# digitalBlock.net
KiCad netlist of a schematic drawn in Altium Designer
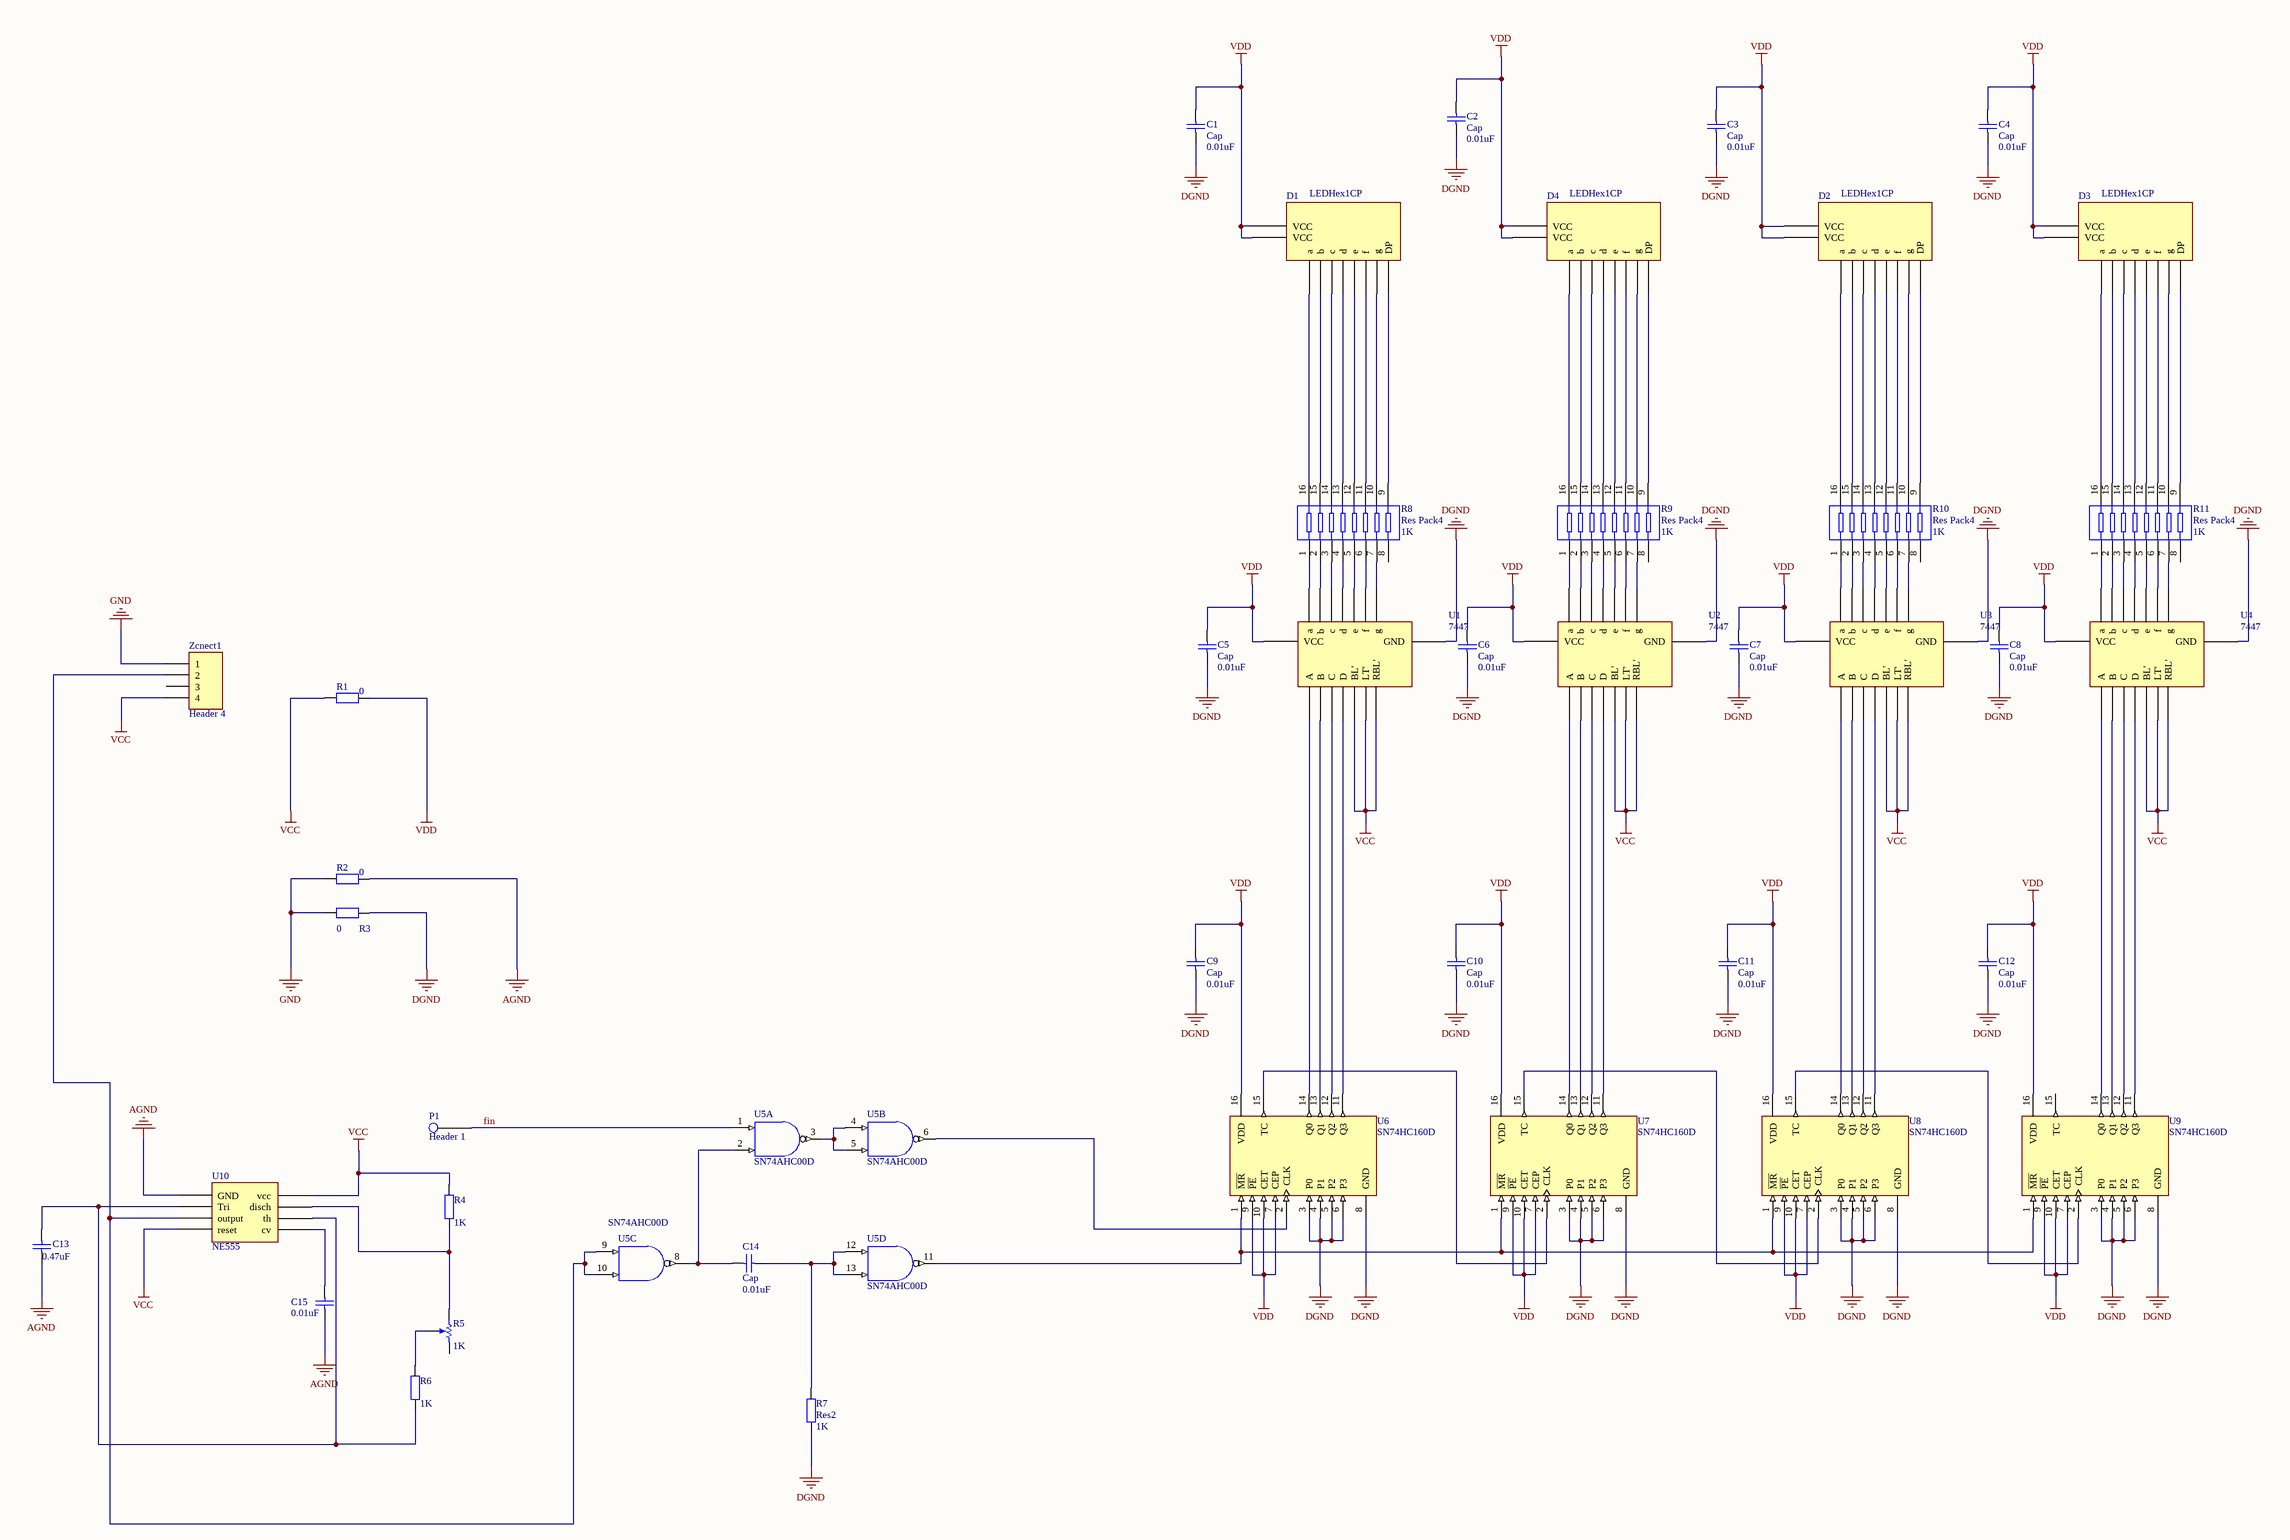
[diagram p0: digitalBlock.SchDoc]

(export (version "E")
  (design (tool "Eeschema 10.0.6"))
  (components
    (comp (ref "C1")
      (value "Cap")
      (footprint "CAP-0603")
      (description "Capacitor")
      (fields (field (name "ALTIUM_VALUE") "0.01uF") (field (name "PUBLISHER") "Altium Limited"))
      (libsource (lib "Miscellaneous Devices") (part "Cap"))
    )
    (comp (ref "C2")
      (value "Cap")
      (footprint "CAP-0603")
      (description "Capacitor")
      (fields (field (name "ALTIUM_VALUE") "0.01uF") (field (name "PUBLISHER") "Altium Limited"))
      (libsource (lib "Miscellaneous Devices") (part "Cap"))
    )
    (comp (ref "C3")
      (value "Cap")
      (footprint "CAP-0603")
      (description "Capacitor")
      (fields (field (name "ALTIUM_VALUE") "0.01uF") (field (name "PUBLISHER") "Altium Limited"))
      (libsource (lib "Miscellaneous Devices") (part "Cap"))
    )
    (comp (ref "C4")
      (value "Cap")
      (footprint "CAP-0603")
      (description "Capacitor")
      (fields (field (name "ALTIUM_VALUE") "0.01uF") (field (name "PUBLISHER") "Altium Limited"))
      (libsource (lib "Miscellaneous Devices") (part "Cap"))
    )
    (comp (ref "C5")
      (value "Cap")
      (footprint "CAP-0603")
      (description "Capacitor")
      (fields (field (name "ALTIUM_VALUE") "0.01uF") (field (name "PUBLISHER") "Altium Limited"))
      (libsource (lib "Miscellaneous Devices") (part "Cap"))
    )
    (comp (ref "C6")
      (value "Cap")
      (footprint "CAP-0603")
      (description "Capacitor")
      (fields (field (name "ALTIUM_VALUE") "0.01uF") (field (name "PUBLISHER") "Altium Limited"))
      (libsource (lib "Miscellaneous Devices") (part "Cap"))
    )
    (comp (ref "C7")
      (value "Cap")
      (footprint "CAP-0603")
      (description "Capacitor")
      (fields (field (name "ALTIUM_VALUE") "0.01uF") (field (name "PUBLISHER") "Altium Limited"))
      (libsource (lib "Miscellaneous Devices") (part "Cap"))
    )
    (comp (ref "C8")
      (value "Cap")
      (footprint "CAP-0603")
      (description "Capacitor")
      (fields (field (name "ALTIUM_VALUE") "0.01uF") (field (name "PUBLISHER") "Altium Limited"))
      (libsource (lib "Miscellaneous Devices") (part "Cap"))
    )
    (comp (ref "C9")
      (value "Cap")
      (footprint "CAP-0603")
      (description "Capacitor")
      (fields (field (name "ALTIUM_VALUE") "0.01uF") (field (name "PUBLISHER") "Altium Limited"))
      (libsource (lib "Miscellaneous Devices") (part "Cap"))
    )
    (comp (ref "C10")
      (value "Cap")
      (footprint "CAP-0603")
      (description "Capacitor")
      (fields (field (name "ALTIUM_VALUE") "0.01uF") (field (name "PUBLISHER") "Altium Limited"))
      (libsource (lib "Miscellaneous Devices") (part "Cap"))
    )
    (comp (ref "C11")
      (value "Cap")
      (footprint "CAP-0603")
      (description "Capacitor")
      (fields (field (name "ALTIUM_VALUE") "0.01uF") (field (name "PUBLISHER") "Altium Limited"))
      (libsource (lib "Miscellaneous Devices") (part "Cap"))
    )
    (comp (ref "C12")
      (value "Cap")
      (footprint "CAP-0603")
      (description "Capacitor")
      (fields (field (name "ALTIUM_VALUE") "0.01uF") (field (name "PUBLISHER") "Altium Limited"))
      (libsource (lib "Miscellaneous Devices") (part "Cap"))
    )
    (comp (ref "C13")
      (value "0.47uF")
      (footprint "CAP-0603")
      (description "Capacitor")
      (fields (field (name "Comment") "Cap") (field (name "PUBLISHER") "Altium Limited"))
      (libsource (lib "Miscellaneous Devices") (part "Cap"))
    )
    (comp (ref "C14")
      (value "Cap")
      (footprint "CAP-0603")
      (description "Capacitor")
      (fields (field (name "ALTIUM_VALUE") "0.01uF") (field (name "PUBLISHER") "Altium Limited"))
      (libsource (lib "Miscellaneous Devices") (part "Cap"))
    )
    (comp (ref "C15")
      (value "0.01uF")
      (footprint "CAP-0603")
      (description "Capacitor")
      (fields (field (name "Comment") "Cap") (field (name "PUBLISHER") "Altium Limited"))
      (libsource (lib "Miscellaneous Devices") (part "Cap"))
    )
    (comp (ref "D1")
      (value "LEDHex1CP")
      (footprint "LEDDIP-10/C5.08RHD")
      (libsource (lib "MLI") (part "LEDHex1CP"))
    )
    (comp (ref "D2")
      (value "LEDHex1CP")
      (footprint "LEDDIP-10/C5.08RHD")
      (libsource (lib "MLI") (part "LEDHex1CP"))
    )
    (comp (ref "D3")
      (value "LEDHex1CP")
      (footprint "LEDDIP-10/C5.08RHD")
      (libsource (lib "MLI") (part "LEDHex1CP"))
    )
    (comp (ref "D4")
      (value "LEDHex1CP")
      (footprint "LEDDIP-10/C5.08RHD")
      (libsource (lib "MLI") (part "LEDHex1CP"))
    )
    (comp (ref "P1") (value "Header 1") (footprint "HDR1*1") (libsource (lib "MLI") (part "Header 1")))
    (comp (ref "R1")
      (value "0")
      (footprint "RES-0603")
      (description "Resistor")
      (fields (field (name "Comment") "Res2") (field (name "PUBLISHER") "Altium Limited"))
      (libsource (lib "Miscellaneous Devices") (part "Res2"))
    )
    (comp (ref "R2")
      (value "0")
      (footprint "RES-0603")
      (description "Resistor")
      (fields (field (name "Comment") "Res2") (field (name "PUBLISHER") "Altium Limited"))
      (libsource (lib "Miscellaneous Devices") (part "Res2"))
    )
    (comp (ref "R3")
      (value "0")
      (footprint "RES-0603")
      (description "Resistor")
      (fields (field (name "Comment") "Res2") (field (name "PUBLISHER") "Altium Limited"))
      (libsource (lib "Miscellaneous Devices") (part "Res2"))
    )
    (comp (ref "R4")
      (value "1K")
      (footprint "RES-0603")
      (description "Resistor")
      (fields (field (name "Comment") "Res2") (field (name "PUBLISHER") "Altium Limited"))
      (libsource (lib "") (part "Res2_1"))
    )
    (comp (ref "R5")
      (value "1K")
      (footprint "VR5")
      (description "Potentiometer")
      (fields (field (name "Comment") "RPot") (field (name "PUBLISHER") "Altium Limited"))
      (libsource (lib "SkyWorks2") (part "RPot"))
    )
    (comp (ref "R6")
      (value "1K")
      (footprint "RES-0603")
      (description "Resistor")
      (fields (field (name "Comment") "Res2") (field (name "PUBLISHER") "Altium Limited"))
      (libsource (lib "") (part "Res2_1"))
    )
    (comp (ref "R7")
      (value "Res2")
      (footprint "RES-0603")
      (description "Resistor")
      (fields (field (name "ALTIUM_VALUE") "1K") (field (name "PUBLISHER") "Altium Limited"))
      (libsource (lib "") (part "Res2_1"))
    )
    (comp (ref "R8")
      (value "Res Pack4")
      (footprint "SSOP16")
      (description "Isolated Resistor Network")
      (fields (field (name "ALTIUM_VALUE") "1K") (field (name "PUBLISHER") "Altium Limited"))
      (libsource (lib "SkyWorks2") (part "Res Pack4"))
    )
    (comp (ref "R9")
      (value "Res Pack4")
      (footprint "SSOP16")
      (description "Isolated Resistor Network")
      (fields (field (name "ALTIUM_VALUE") "1K") (field (name "PUBLISHER") "Altium Limited"))
      (libsource (lib "SkyWorks2") (part "Res Pack4"))
    )
    (comp (ref "R10")
      (value "Res Pack4")
      (footprint "SSOP16")
      (description "Isolated Resistor Network")
      (fields (field (name "ALTIUM_VALUE") "1K") (field (name "PUBLISHER") "Altium Limited"))
      (libsource (lib "SkyWorks2") (part "Res Pack4"))
    )
    (comp (ref "R11")
      (value "Res Pack4")
      (footprint "SSOP16")
      (description "Isolated Resistor Network")
      (fields (field (name "ALTIUM_VALUE") "1K") (field (name "PUBLISHER") "Altium Limited"))
      (libsource (lib "SkyWorks2") (part "Res Pack4"))
    )
    (comp (ref "U1") (value "7447") (footprint "SO-16") (libsource (lib "MLI") (part "7447")))
    (comp (ref "U2") (value "7447") (footprint "SO-16") (libsource (lib "MLI") (part "7447")))
    (comp (ref "U3") (value "7447") (footprint "SO-16") (libsource (lib "MLI") (part "7447")))
    (comp (ref "U4") (value "7447") (footprint "SO-16") (libsource (lib "MLI") (part "7447")))
    (comp (ref "U5")
      (value "SN74AHC00D")
      (footprint "SO-14")
      (description "Quadruple 2-Input Positive-NAND Gate")
      (fields (field (name "PUBLISHER") "Altium Limited"))
      (libsource (lib "TI Logic Gate 1") (part "SN74AHC00D"))
    )
    (comp (ref "U6")
      (value "SN74HC160D")
      (footprint "SO-16")
      (description "Synchronous 4-Bit Decade and Binary Counter")
      (fields (field (name "PUBLISHER") "Altium Limited"))
      (libsource (lib "TI Logic Counter") (part "SN74HC160D"))
    )
    (comp (ref "U7")
      (value "SN74HC160D")
      (footprint "SO-16")
      (description "Synchronous 4-Bit Decade and Binary Counter")
      (fields (field (name "PUBLISHER") "Altium Limited"))
      (libsource (lib "TI Logic Counter") (part "SN74HC160D"))
    )
    (comp (ref "U8")
      (value "SN74HC160D")
      (footprint "SO-16")
      (description "Synchronous 4-Bit Decade and Binary Counter")
      (fields (field (name "PUBLISHER") "Altium Limited"))
      (libsource (lib "TI Logic Counter") (part "SN74HC160D"))
    )
    (comp (ref "U9")
      (value "SN74HC160D")
      (footprint "SO-16")
      (description "Synchronous 4-Bit Decade and Binary Counter")
      (fields (field (name "PUBLISHER") "Altium Limited"))
      (libsource (lib "TI Logic Counter") (part "SN74HC160D"))
    )
    (comp (ref "U10") (value "NE555") (footprint "SO-8") (libsource (lib "MLI") (part "NE555")))
    (comp (ref "Zcnect1")
      (value "Header 4")
      (footprint "HDR1X4")
      (description "Header, 4-Pin")
      (fields (field (name "PUBLISHER") "Altium Limited"))
      (libsource (lib "SkyWorks2") (part "Header 4"))
    )
  )
  (nets
    (net (code "1") (name "/fin") (class "Default")
      (node (ref "P1") (pin "1") (pinfunction "p_1") (pintype "passive"))
      (node (ref "U5") (pin "1") (pinfunction "A_1") (pintype "input"))
    )
    (net (code "2") (name "AGND") (class "Default")
      (node (ref "C13") (pin "1") (pinfunction "1_1") (pintype "passive"))
      (node (ref "C15") (pin "1") (pinfunction "1_1") (pintype "passive"))
      (node (ref "R2") (pin "2") (pinfunction "2_2") (pintype "passive"))
      (node (ref "U10") (pin "1") (pinfunction "GND_1") (pintype "passive"))
    )
    (net (code "3") (name "DGND") (class "Default")
      (node (ref "C1") (pin "1") (pinfunction "1_1") (pintype "passive"))
      (node (ref "C10") (pin "1") (pinfunction "1_1") (pintype "passive"))
      (node (ref "C11") (pin "1") (pinfunction "1_1") (pintype "passive"))
      (node (ref "C12") (pin "1") (pinfunction "1_1") (pintype "passive"))
      (node (ref "C2") (pin "1") (pinfunction "1_1") (pintype "passive"))
      (node (ref "C3") (pin "1") (pinfunction "1_1") (pintype "passive"))
      (node (ref "C4") (pin "1") (pinfunction "1_1") (pintype "passive"))
      (node (ref "C5") (pin "1") (pinfunction "1_1") (pintype "passive"))
      (node (ref "C6") (pin "1") (pinfunction "1_1") (pintype "passive"))
      (node (ref "C7") (pin "1") (pinfunction "1_1") (pintype "passive"))
      (node (ref "C8") (pin "1") (pinfunction "1_1") (pintype "passive"))
      (node (ref "C9") (pin "1") (pinfunction "1_1") (pintype "passive"))
      (node (ref "R3") (pin "2") (pinfunction "2_2") (pintype "passive"))
      (node (ref "R7") (pin "1") (pinfunction "1_1") (pintype "passive"))
      (node (ref "U1") (pin "8") (pinfunction "GND_8") (pintype "passive"))
      (node (ref "U2") (pin "8") (pinfunction "GND_8") (pintype "passive"))
      (node (ref "U3") (pin "8") (pinfunction "GND_8") (pintype "passive"))
      (node (ref "U4") (pin "8") (pinfunction "GND_8") (pintype "passive"))
      (node (ref "U6") (pin "3") (pinfunction "P0_3") (pintype "input"))
      (node (ref "U6") (pin "4") (pinfunction "P1_4") (pintype "input"))
      (node (ref "U6") (pin "5") (pinfunction "P2_5") (pintype "input"))
      (node (ref "U6") (pin "6") (pinfunction "P3_6") (pintype "input"))
      (node (ref "U6") (pin "8") (pinfunction "GND_8") (pintype "power_in"))
      (node (ref "U7") (pin "3") (pinfunction "P0_3") (pintype "input"))
      (node (ref "U7") (pin "4") (pinfunction "P1_4") (pintype "input"))
      (node (ref "U7") (pin "5") (pinfunction "P2_5") (pintype "input"))
      (node (ref "U7") (pin "6") (pinfunction "P3_6") (pintype "input"))
      (node (ref "U7") (pin "8") (pinfunction "GND_8") (pintype "power_in"))
      (node (ref "U8") (pin "3") (pinfunction "P0_3") (pintype "input"))
      (node (ref "U8") (pin "4") (pinfunction "P1_4") (pintype "input"))
      (node (ref "U8") (pin "5") (pinfunction "P2_5") (pintype "input"))
      (node (ref "U8") (pin "6") (pinfunction "P3_6") (pintype "input"))
      (node (ref "U8") (pin "8") (pinfunction "GND_8") (pintype "power_in"))
      (node (ref "U9") (pin "3") (pinfunction "P0_3") (pintype "input"))
      (node (ref "U9") (pin "4") (pinfunction "P1_4") (pintype "input"))
      (node (ref "U9") (pin "5") (pinfunction "P2_5") (pintype "input"))
      (node (ref "U9") (pin "6") (pinfunction "P3_6") (pintype "input"))
      (node (ref "U9") (pin "8") (pinfunction "GND_8") (pintype "power_in"))
    )
    (net (code "4") (name "GND") (class "Default")
      (node (ref "R2") (pin "1") (pinfunction "1_1") (pintype "passive"))
      (node (ref "R3") (pin "1") (pinfunction "1_1") (pintype "passive"))
      (node (ref "U5") (pin "7") (pinfunction "GND_7") (pintype "power_in"))
      (node (ref "Zcnect1") (pin "1") (pinfunction "1_1") (pintype "passive"))
    )
    (net (code "5") (name "Net-(D1-DP)") (class "Default")
      (node (ref "D1") (pin "7") (pinfunction "DP_7") (pintype "passive"))
      (node (ref "R8") (pin "9") (pinfunction "9_9") (pintype "passive"))
    )
    (net (code "6") (name "Net-(D1-a)") (class "Default")
      (node (ref "D1") (pin "10") (pinfunction "a_10") (pintype "passive"))
      (node (ref "R8") (pin "16") (pinfunction "16_16") (pintype "passive"))
    )
    (net (code "7") (name "Net-(D1-b)") (class "Default")
      (node (ref "D1") (pin "9") (pinfunction "b_9") (pintype "passive"))
      (node (ref "R8") (pin "15") (pinfunction "15_15") (pintype "passive"))
    )
    (net (code "8") (name "Net-(D1-c)") (class "Default")
      (node (ref "D1") (pin "8") (pinfunction "c_8") (pintype "passive"))
      (node (ref "R8") (pin "14") (pinfunction "14_14") (pintype "passive"))
    )
    (net (code "9") (name "Net-(D1-d)") (class "Default")
      (node (ref "D1") (pin "5") (pinfunction "d_5") (pintype "passive"))
      (node (ref "R8") (pin "13") (pinfunction "13_13") (pintype "passive"))
    )
    (net (code "10") (name "Net-(D1-e)") (class "Default")
      (node (ref "D1") (pin "4") (pinfunction "e_4") (pintype "passive"))
      (node (ref "R8") (pin "12") (pinfunction "12_12") (pintype "passive"))
    )
    (net (code "11") (name "Net-(D1-f)") (class "Default")
      (node (ref "D1") (pin "2") (pinfunction "f_2") (pintype "passive"))
      (node (ref "R8") (pin "11") (pinfunction "11_11") (pintype "passive"))
    )
    (net (code "12") (name "Net-(D1-g)") (class "Default")
      (node (ref "D1") (pin "3") (pinfunction "g_3") (pintype "passive"))
      (node (ref "R8") (pin "10") (pinfunction "10_10") (pintype "passive"))
    )
    (net (code "13") (name "Net-(D2-DP)") (class "Default")
      (node (ref "D2") (pin "7") (pinfunction "DP_7") (pintype "passive"))
      (node (ref "R10") (pin "9") (pinfunction "9_9") (pintype "passive"))
    )
    (net (code "14") (name "Net-(D2-a)") (class "Default")
      (node (ref "D2") (pin "10") (pinfunction "a_10") (pintype "passive"))
      (node (ref "R10") (pin "16") (pinfunction "16_16") (pintype "passive"))
    )
    (net (code "15") (name "Net-(D2-b)") (class "Default")
      (node (ref "D2") (pin "9") (pinfunction "b_9") (pintype "passive"))
      (node (ref "R10") (pin "15") (pinfunction "15_15") (pintype "passive"))
    )
    (net (code "16") (name "Net-(D2-c)") (class "Default")
      (node (ref "D2") (pin "8") (pinfunction "c_8") (pintype "passive"))
      (node (ref "R10") (pin "14") (pinfunction "14_14") (pintype "passive"))
    )
    (net (code "17") (name "Net-(D2-d)") (class "Default")
      (node (ref "D2") (pin "5") (pinfunction "d_5") (pintype "passive"))
      (node (ref "R10") (pin "13") (pinfunction "13_13") (pintype "passive"))
    )
    (net (code "18") (name "Net-(D2-e)") (class "Default")
      (node (ref "D2") (pin "4") (pinfunction "e_4") (pintype "passive"))
      (node (ref "R10") (pin "12") (pinfunction "12_12") (pintype "passive"))
    )
    (net (code "19") (name "Net-(D2-f)") (class "Default")
      (node (ref "D2") (pin "2") (pinfunction "f_2") (pintype "passive"))
      (node (ref "R10") (pin "11") (pinfunction "11_11") (pintype "passive"))
    )
    (net (code "20") (name "Net-(D2-g)") (class "Default")
      (node (ref "D2") (pin "3") (pinfunction "g_3") (pintype "passive"))
      (node (ref "R10") (pin "10") (pinfunction "10_10") (pintype "passive"))
    )
    (net (code "21") (name "Net-(D3-DP)") (class "Default")
      (node (ref "D3") (pin "7") (pinfunction "DP_7") (pintype "passive"))
      (node (ref "R11") (pin "9") (pinfunction "9_9") (pintype "passive"))
    )
    (net (code "22") (name "Net-(D3-a)") (class "Default")
      (node (ref "D3") (pin "10") (pinfunction "a_10") (pintype "passive"))
      (node (ref "R11") (pin "16") (pinfunction "16_16") (pintype "passive"))
    )
    (net (code "23") (name "Net-(D3-b)") (class "Default")
      (node (ref "D3") (pin "9") (pinfunction "b_9") (pintype "passive"))
      (node (ref "R11") (pin "15") (pinfunction "15_15") (pintype "passive"))
    )
    (net (code "24") (name "Net-(D3-c)") (class "Default")
      (node (ref "D3") (pin "8") (pinfunction "c_8") (pintype "passive"))
      (node (ref "R11") (pin "14") (pinfunction "14_14") (pintype "passive"))
    )
    (net (code "25") (name "Net-(D3-d)") (class "Default")
      (node (ref "D3") (pin "5") (pinfunction "d_5") (pintype "passive"))
      (node (ref "R11") (pin "13") (pinfunction "13_13") (pintype "passive"))
    )
    (net (code "26") (name "Net-(D3-e)") (class "Default")
      (node (ref "D3") (pin "4") (pinfunction "e_4") (pintype "passive"))
      (node (ref "R11") (pin "12") (pinfunction "12_12") (pintype "passive"))
    )
    (net (code "27") (name "Net-(D3-f)") (class "Default")
      (node (ref "D3") (pin "2") (pinfunction "f_2") (pintype "passive"))
      (node (ref "R11") (pin "11") (pinfunction "11_11") (pintype "passive"))
    )
    (net (code "28") (name "Net-(D3-g)") (class "Default")
      (node (ref "D3") (pin "3") (pinfunction "g_3") (pintype "passive"))
      (node (ref "R11") (pin "10") (pinfunction "10_10") (pintype "passive"))
    )
    (net (code "29") (name "Net-(D4-DP)") (class "Default")
      (node (ref "D4") (pin "7") (pinfunction "DP_7") (pintype "passive"))
      (node (ref "R9") (pin "9") (pinfunction "9_9") (pintype "passive"))
    )
    (net (code "30") (name "Net-(D4-a)") (class "Default")
      (node (ref "D4") (pin "10") (pinfunction "a_10") (pintype "passive"))
      (node (ref "R9") (pin "16") (pinfunction "16_16") (pintype "passive"))
    )
    (net (code "31") (name "Net-(D4-b)") (class "Default")
      (node (ref "D4") (pin "9") (pinfunction "b_9") (pintype "passive"))
      (node (ref "R9") (pin "15") (pinfunction "15_15") (pintype "passive"))
    )
    (net (code "32") (name "Net-(D4-c)") (class "Default")
      (node (ref "D4") (pin "8") (pinfunction "c_8") (pintype "passive"))
      (node (ref "R9") (pin "14") (pinfunction "14_14") (pintype "passive"))
    )
    (net (code "33") (name "Net-(D4-d)") (class "Default")
      (node (ref "D4") (pin "5") (pinfunction "d_5") (pintype "passive"))
      (node (ref "R9") (pin "13") (pinfunction "13_13") (pintype "passive"))
    )
    (net (code "34") (name "Net-(D4-e)") (class "Default")
      (node (ref "D4") (pin "4") (pinfunction "e_4") (pintype "passive"))
      (node (ref "R9") (pin "12") (pinfunction "12_12") (pintype "passive"))
    )
    (net (code "35") (name "Net-(D4-f)") (class "Default")
      (node (ref "D4") (pin "2") (pinfunction "f_2") (pintype "passive"))
      (node (ref "R9") (pin "11") (pinfunction "11_11") (pintype "passive"))
    )
    (net (code "36") (name "Net-(D4-g)") (class "Default")
      (node (ref "D4") (pin "3") (pinfunction "g_3") (pintype "passive"))
      (node (ref "R9") (pin "10") (pinfunction "10_10") (pintype "passive"))
    )
    (net (code "37") (name "Net-(R5-TAP)") (class "Default")
      (node (ref "R5") (pin "3") (pinfunction "TAP_3") (pintype "passive"))
      (node (ref "R6") (pin "2") (pinfunction "2_2") (pintype "passive"))
    )
    (net (code "38") (name "Net-(R5-TOP)") (class "Default")
      (node (ref "R4") (pin "1") (pinfunction "1_1") (pintype "passive"))
      (node (ref "R5") (pin "1") (pinfunction "TOP_1") (pintype "passive"))
      (node (ref "U10") (pin "7") (pinfunction "disch_7") (pintype "passive"))
    )
    (net (code "39") (name "Net-(U1-A)") (class "Default")
      (node (ref "U1") (pin "7") (pinfunction "A_7") (pintype "passive"))
      (node (ref "U6") (pin "14") (pinfunction "Q0_14") (pintype "output"))
    )
    (net (code "40") (name "Net-(U1-B)") (class "Default")
      (node (ref "U1") (pin "1") (pinfunction "B_1") (pintype "passive"))
      (node (ref "U6") (pin "13") (pinfunction "Q1_13") (pintype "output"))
    )
    (net (code "41") (name "Net-(U1-C)") (class "Default")
      (node (ref "U1") (pin "2") (pinfunction "C_2") (pintype "passive"))
      (node (ref "U6") (pin "12") (pinfunction "Q2_12") (pintype "output"))
    )
    (net (code "42") (name "Net-(U1-D)") (class "Default")
      (node (ref "U1") (pin "6") (pinfunction "D_6") (pintype "passive"))
      (node (ref "U6") (pin "11") (pinfunction "Q3_11") (pintype "output"))
    )
    (net (code "43") (name "Net-(U1-a)") (class "Default")
      (node (ref "R8") (pin "1") (pinfunction "1_1") (pintype "passive"))
      (node (ref "U1") (pin "13") (pinfunction "a_13") (pintype "passive"))
    )
    (net (code "44") (name "Net-(U1-b)") (class "Default")
      (node (ref "R8") (pin "2") (pinfunction "2_2") (pintype "passive"))
      (node (ref "U1") (pin "12") (pinfunction "b_12") (pintype "passive"))
    )
    (net (code "45") (name "Net-(U1-c)") (class "Default")
      (node (ref "R8") (pin "3") (pinfunction "3_3") (pintype "passive"))
      (node (ref "U1") (pin "11") (pinfunction "c_11") (pintype "passive"))
    )
    (net (code "46") (name "Net-(U1-d)") (class "Default")
      (node (ref "R8") (pin "4") (pinfunction "4_4") (pintype "passive"))
      (node (ref "U1") (pin "10") (pinfunction "d_10") (pintype "passive"))
    )
    (net (code "47") (name "Net-(U1-e)") (class "Default")
      (node (ref "R8") (pin "5") (pinfunction "5_5") (pintype "passive"))
      (node (ref "U1") (pin "9") (pinfunction "e_9") (pintype "passive"))
    )
    (net (code "48") (name "Net-(U1-f)") (class "Default")
      (node (ref "R8") (pin "6") (pinfunction "6_6") (pintype "passive"))
      (node (ref "U1") (pin "15") (pinfunction "f_15") (pintype "passive"))
    )
    (net (code "49") (name "Net-(U1-g)") (class "Default")
      (node (ref "R8") (pin "7") (pinfunction "7_7") (pintype "passive"))
      (node (ref "U1") (pin "14") (pinfunction "g_14") (pintype "passive"))
    )
    (net (code "50") (name "Net-(U2-A)") (class "Default")
      (node (ref "U2") (pin "7") (pinfunction "A_7") (pintype "passive"))
      (node (ref "U7") (pin "14") (pinfunction "Q0_14") (pintype "output"))
    )
    (net (code "51") (name "Net-(U2-B)") (class "Default")
      (node (ref "U2") (pin "1") (pinfunction "B_1") (pintype "passive"))
      (node (ref "U7") (pin "13") (pinfunction "Q1_13") (pintype "output"))
    )
    (net (code "52") (name "Net-(U2-C)") (class "Default")
      (node (ref "U2") (pin "2") (pinfunction "C_2") (pintype "passive"))
      (node (ref "U7") (pin "12") (pinfunction "Q2_12") (pintype "output"))
    )
    (net (code "53") (name "Net-(U2-D)") (class "Default")
      (node (ref "U2") (pin "6") (pinfunction "D_6") (pintype "passive"))
      (node (ref "U7") (pin "11") (pinfunction "Q3_11") (pintype "output"))
    )
    (net (code "54") (name "Net-(U2-a)") (class "Default")
      (node (ref "R9") (pin "1") (pinfunction "1_1") (pintype "passive"))
      (node (ref "U2") (pin "13") (pinfunction "a_13") (pintype "passive"))
    )
    (net (code "55") (name "Net-(U2-b)") (class "Default")
      (node (ref "R9") (pin "2") (pinfunction "2_2") (pintype "passive"))
      (node (ref "U2") (pin "12") (pinfunction "b_12") (pintype "passive"))
    )
    (net (code "56") (name "Net-(U2-c)") (class "Default")
      (node (ref "R9") (pin "3") (pinfunction "3_3") (pintype "passive"))
      (node (ref "U2") (pin "11") (pinfunction "c_11") (pintype "passive"))
    )
    (net (code "57") (name "Net-(U2-d)") (class "Default")
      (node (ref "R9") (pin "4") (pinfunction "4_4") (pintype "passive"))
      (node (ref "U2") (pin "10") (pinfunction "d_10") (pintype "passive"))
    )
    (net (code "58") (name "Net-(U2-e)") (class "Default")
      (node (ref "R9") (pin "5") (pinfunction "5_5") (pintype "passive"))
      (node (ref "U2") (pin "9") (pinfunction "e_9") (pintype "passive"))
    )
    (net (code "59") (name "Net-(U2-f)") (class "Default")
      (node (ref "R9") (pin "6") (pinfunction "6_6") (pintype "passive"))
      (node (ref "U2") (pin "15") (pinfunction "f_15") (pintype "passive"))
    )
    (net (code "60") (name "Net-(U2-g)") (class "Default")
      (node (ref "R9") (pin "7") (pinfunction "7_7") (pintype "passive"))
      (node (ref "U2") (pin "14") (pinfunction "g_14") (pintype "passive"))
    )
    (net (code "61") (name "Net-(U3-A)") (class "Default")
      (node (ref "U3") (pin "7") (pinfunction "A_7") (pintype "passive"))
      (node (ref "U8") (pin "14") (pinfunction "Q0_14") (pintype "output"))
    )
    (net (code "62") (name "Net-(U3-B)") (class "Default")
      (node (ref "U3") (pin "1") (pinfunction "B_1") (pintype "passive"))
      (node (ref "U8") (pin "13") (pinfunction "Q1_13") (pintype "output"))
    )
    (net (code "63") (name "Net-(U3-C)") (class "Default")
      (node (ref "U3") (pin "2") (pinfunction "C_2") (pintype "passive"))
      (node (ref "U8") (pin "12") (pinfunction "Q2_12") (pintype "output"))
    )
    (net (code "64") (name "Net-(U3-D)") (class "Default")
      (node (ref "U3") (pin "6") (pinfunction "D_6") (pintype "passive"))
      (node (ref "U8") (pin "11") (pinfunction "Q3_11") (pintype "output"))
    )
    (net (code "65") (name "Net-(U3-a)") (class "Default")
      (node (ref "R10") (pin "1") (pinfunction "1_1") (pintype "passive"))
      (node (ref "U3") (pin "13") (pinfunction "a_13") (pintype "passive"))
    )
    (net (code "66") (name "Net-(U3-b)") (class "Default")
      (node (ref "R10") (pin "2") (pinfunction "2_2") (pintype "passive"))
      (node (ref "U3") (pin "12") (pinfunction "b_12") (pintype "passive"))
    )
    (net (code "67") (name "Net-(U3-c)") (class "Default")
      (node (ref "R10") (pin "3") (pinfunction "3_3") (pintype "passive"))
      (node (ref "U3") (pin "11") (pinfunction "c_11") (pintype "passive"))
    )
    (net (code "68") (name "Net-(U3-d)") (class "Default")
      (node (ref "R10") (pin "4") (pinfunction "4_4") (pintype "passive"))
      (node (ref "U3") (pin "10") (pinfunction "d_10") (pintype "passive"))
    )
    (net (code "69") (name "Net-(U3-e)") (class "Default")
      (node (ref "R10") (pin "5") (pinfunction "5_5") (pintype "passive"))
      (node (ref "U3") (pin "9") (pinfunction "e_9") (pintype "passive"))
    )
    (net (code "70") (name "Net-(U3-f)") (class "Default")
      (node (ref "R10") (pin "6") (pinfunction "6_6") (pintype "passive"))
      (node (ref "U3") (pin "15") (pinfunction "f_15") (pintype "passive"))
    )
    (net (code "71") (name "Net-(U3-g)") (class "Default")
      (node (ref "R10") (pin "7") (pinfunction "7_7") (pintype "passive"))
      (node (ref "U3") (pin "14") (pinfunction "g_14") (pintype "passive"))
    )
    (net (code "72") (name "Net-(U4-A)") (class "Default")
      (node (ref "U4") (pin "7") (pinfunction "A_7") (pintype "passive"))
      (node (ref "U9") (pin "14") (pinfunction "Q0_14") (pintype "output"))
    )
    (net (code "73") (name "Net-(U4-B)") (class "Default")
      (node (ref "U4") (pin "1") (pinfunction "B_1") (pintype "passive"))
      (node (ref "U9") (pin "13") (pinfunction "Q1_13") (pintype "output"))
    )
    (net (code "74") (name "Net-(U4-C)") (class "Default")
      (node (ref "U4") (pin "2") (pinfunction "C_2") (pintype "passive"))
      (node (ref "U9") (pin "12") (pinfunction "Q2_12") (pintype "output"))
    )
    (net (code "75") (name "Net-(U4-D)") (class "Default")
      (node (ref "U4") (pin "6") (pinfunction "D_6") (pintype "passive"))
      (node (ref "U9") (pin "11") (pinfunction "Q3_11") (pintype "output"))
    )
    (net (code "76") (name "Net-(U4-a)") (class "Default")
      (node (ref "R11") (pin "1") (pinfunction "1_1") (pintype "passive"))
      (node (ref "U4") (pin "13") (pinfunction "a_13") (pintype "passive"))
    )
    (net (code "77") (name "Net-(U4-b)") (class "Default")
      (node (ref "R11") (pin "2") (pinfunction "2_2") (pintype "passive"))
      (node (ref "U4") (pin "12") (pinfunction "b_12") (pintype "passive"))
    )
    (net (code "78") (name "Net-(U4-c)") (class "Default")
      (node (ref "R11") (pin "3") (pinfunction "3_3") (pintype "passive"))
      (node (ref "U4") (pin "11") (pinfunction "c_11") (pintype "passive"))
    )
    (net (code "79") (name "Net-(U4-d)") (class "Default")
      (node (ref "R11") (pin "4") (pinfunction "4_4") (pintype "passive"))
      (node (ref "U4") (pin "10") (pinfunction "d_10") (pintype "passive"))
    )
    (net (code "80") (name "Net-(U4-e)") (class "Default")
      (node (ref "R11") (pin "5") (pinfunction "5_5") (pintype "passive"))
      (node (ref "U4") (pin "9") (pinfunction "e_9") (pintype "passive"))
    )
    (net (code "81") (name "Net-(U4-f)") (class "Default")
      (node (ref "R11") (pin "6") (pinfunction "6_6") (pintype "passive"))
      (node (ref "U4") (pin "15") (pinfunction "f_15") (pintype "passive"))
    )
    (net (code "82") (name "Net-(U4-g)") (class "Default")
      (node (ref "R11") (pin "7") (pinfunction "7_7") (pintype "passive"))
      (node (ref "U4") (pin "14") (pinfunction "g_14") (pintype "passive"))
    )
    (net (code "83") (name "Net-(U5A-B)") (class "Default")
      (node (ref "C14") (pin "2") (pinfunction "2_2") (pintype "passive"))
      (node (ref "U5") (pin "2") (pinfunction "B_2") (pintype "input"))
      (node (ref "U5") (pin "8") (pinfunction "Y_8") (pintype "output"))
    )
    (net (code "84") (name "Net-(U5A-Y)") (class "Default")
      (node (ref "U5") (pin "3") (pinfunction "Y_3") (pintype "output"))
      (node (ref "U5") (pin "4") (pinfunction "A_4") (pintype "input"))
      (node (ref "U5") (pin "5") (pinfunction "B_5") (pintype "input"))
    )
    (net (code "85") (name "Net-(U5B-Y)") (class "Default")
      (node (ref "U5") (pin "6") (pinfunction "Y_6") (pintype "output"))
      (node (ref "U6") (pin "2") (pinfunction "CLK_2") (pintype "input"))
    )
    (net (code "86") (name "Net-(U5D-A)") (class "Default")
      (node (ref "C14") (pin "1") (pinfunction "1_1") (pintype "passive"))
      (node (ref "R7") (pin "2") (pinfunction "2_2") (pintype "passive"))
      (node (ref "U5") (pin "12") (pinfunction "A_12") (pintype "input"))
      (node (ref "U5") (pin "13") (pinfunction "B_13") (pintype "input"))
    )
    (net (code "87") (name "Net-(U5D-Y)") (class "Default")
      (node (ref "U5") (pin "11") (pinfunction "Y_11") (pintype "output"))
      (node (ref "U6") (pin "1") (pinfunction "~{MR}_1") (pintype "input"))
      (node (ref "U7") (pin "1") (pinfunction "~{MR}_1") (pintype "input"))
      (node (ref "U8") (pin "1") (pinfunction "~{MR}_1") (pintype "input"))
      (node (ref "U9") (pin "1") (pinfunction "~{MR}_1") (pintype "input"))
    )
    (net (code "88") (name "Net-(U6-TC)") (class "Default")
      (node (ref "U6") (pin "15") (pinfunction "TC_15") (pintype "output"))
      (node (ref "U7") (pin "2") (pinfunction "CLK_2") (pintype "input"))
    )
    (net (code "89") (name "Net-(U7-TC)") (class "Default")
      (node (ref "U7") (pin "15") (pinfunction "TC_15") (pintype "output"))
      (node (ref "U8") (pin "2") (pinfunction "CLK_2") (pintype "input"))
    )
    (net (code "90") (name "Net-(U8-TC)") (class "Default")
      (node (ref "U8") (pin "15") (pinfunction "TC_15") (pintype "output"))
      (node (ref "U9") (pin "2") (pinfunction "CLK_2") (pintype "input"))
    )
    (net (code "91") (name "Net-(U10-Tri)") (class "Default")
      (node (ref "C13") (pin "2") (pinfunction "2_2") (pintype "passive"))
      (node (ref "R6") (pin "1") (pinfunction "1_1") (pintype "passive"))
      (node (ref "U10") (pin "2") (pinfunction "Tri_2") (pintype "passive"))
      (node (ref "U10") (pin "6") (pinfunction "th_6") (pintype "passive"))
    )
    (net (code "92") (name "Net-(U10-cv)") (class "Default")
      (node (ref "C15") (pin "2") (pinfunction "2_2") (pintype "passive"))
      (node (ref "U10") (pin "5") (pinfunction "cv_5") (pintype "passive"))
    )
    (net (code "93") (name "Net-(U10-output)") (class "Default")
      (node (ref "U10") (pin "3") (pinfunction "output_3") (pintype "passive"))
      (node (ref "U5") (pin "10") (pinfunction "B_10") (pintype "input"))
      (node (ref "U5") (pin "9") (pinfunction "A_9") (pintype "input"))
      (node (ref "Zcnect1") (pin "2") (pinfunction "2_2") (pintype "passive"))
    )
    (net (code "94") (name "VCC") (class "Default")
      (node (ref "R1") (pin "1") (pinfunction "1_1") (pintype "passive"))
      (node (ref "R4") (pin "2") (pinfunction "2_2") (pintype "passive"))
      (node (ref "U1") (pin "3") (pinfunction "LT'_3") (pintype "passive"))
      (node (ref "U1") (pin "4") (pinfunction "BL'_4") (pintype "passive"))
      (node (ref "U1") (pin "5") (pinfunction "RBL'_5") (pintype "passive"))
      (node (ref "U10") (pin "4") (pinfunction "reset_4") (pintype "passive"))
      (node (ref "U10") (pin "8") (pinfunction "vcc_8") (pintype "passive"))
      (node (ref "U2") (pin "3") (pinfunction "LT'_3") (pintype "passive"))
      (node (ref "U2") (pin "4") (pinfunction "BL'_4") (pintype "passive"))
      (node (ref "U2") (pin "5") (pinfunction "RBL'_5") (pintype "passive"))
      (node (ref "U3") (pin "3") (pinfunction "LT'_3") (pintype "passive"))
      (node (ref "U3") (pin "4") (pinfunction "BL'_4") (pintype "passive"))
      (node (ref "U3") (pin "5") (pinfunction "RBL'_5") (pintype "passive"))
      (node (ref "U4") (pin "3") (pinfunction "LT'_3") (pintype "passive"))
      (node (ref "U4") (pin "4") (pinfunction "BL'_4") (pintype "passive"))
      (node (ref "U4") (pin "5") (pinfunction "RBL'_5") (pintype "passive"))
      (node (ref "U5") (pin "14") (pinfunction "VCC_14") (pintype "power_in"))
      (node (ref "Zcnect1") (pin "4") (pinfunction "4_4") (pintype "passive"))
    )
    (net (code "95") (name "VDD") (class "Default")
      (node (ref "C1") (pin "2") (pinfunction "2_2") (pintype "passive"))
      (node (ref "C10") (pin "2") (pinfunction "2_2") (pintype "passive"))
      (node (ref "C11") (pin "2") (pinfunction "2_2") (pintype "passive"))
      (node (ref "C12") (pin "2") (pinfunction "2_2") (pintype "passive"))
      (node (ref "C2") (pin "2") (pinfunction "2_2") (pintype "passive"))
      (node (ref "C3") (pin "2") (pinfunction "2_2") (pintype "passive"))
      (node (ref "C4") (pin "2") (pinfunction "2_2") (pintype "passive"))
      (node (ref "C5") (pin "2") (pinfunction "2_2") (pintype "passive"))
      (node (ref "C6") (pin "2") (pinfunction "2_2") (pintype "passive"))
      (node (ref "C7") (pin "2") (pinfunction "2_2") (pintype "passive"))
      (node (ref "C8") (pin "2") (pinfunction "2_2") (pintype "passive"))
      (node (ref "C9") (pin "2") (pinfunction "2_2") (pintype "passive"))
      (node (ref "D1") (pin "1") (pinfunction "VCC_1") (pintype "passive"))
      (node (ref "D1") (pin "6") (pinfunction "VCC_6") (pintype "passive"))
      (node (ref "D2") (pin "1") (pinfunction "VCC_1") (pintype "passive"))
      (node (ref "D2") (pin "6") (pinfunction "VCC_6") (pintype "passive"))
      (node (ref "D3") (pin "1") (pinfunction "VCC_1") (pintype "passive"))
      (node (ref "D3") (pin "6") (pinfunction "VCC_6") (pintype "passive"))
      (node (ref "D4") (pin "1") (pinfunction "VCC_1") (pintype "passive"))
      (node (ref "D4") (pin "6") (pinfunction "VCC_6") (pintype "passive"))
      (node (ref "R1") (pin "2") (pinfunction "2_2") (pintype "passive"))
      (node (ref "U1") (pin "16") (pinfunction "VCC_16") (pintype "passive"))
      (node (ref "U2") (pin "16") (pinfunction "VCC_16") (pintype "passive"))
      (node (ref "U3") (pin "16") (pinfunction "VCC_16") (pintype "passive"))
      (node (ref "U4") (pin "16") (pinfunction "VCC_16") (pintype "passive"))
      (node (ref "U6") (pin "10") (pinfunction "CET_10") (pintype "input"))
      (node (ref "U6") (pin "16") (pinfunction "VDD_16") (pintype "power_in"))
      (node (ref "U6") (pin "7") (pinfunction "CEP_7") (pintype "input"))
      (node (ref "U6") (pin "9") (pinfunction "~{PE}_9") (pintype "input"))
      (node (ref "U7") (pin "10") (pinfunction "CET_10") (pintype "input"))
      (node (ref "U7") (pin "16") (pinfunction "VDD_16") (pintype "power_in"))
      (node (ref "U7") (pin "7") (pinfunction "CEP_7") (pintype "input"))
      (node (ref "U7") (pin "9") (pinfunction "~{PE}_9") (pintype "input"))
      (node (ref "U8") (pin "10") (pinfunction "CET_10") (pintype "input"))
      (node (ref "U8") (pin "16") (pinfunction "VDD_16") (pintype "power_in"))
      (node (ref "U8") (pin "7") (pinfunction "CEP_7") (pintype "input"))
      (node (ref "U8") (pin "9") (pinfunction "~{PE}_9") (pintype "input"))
      (node (ref "U9") (pin "10") (pinfunction "CET_10") (pintype "input"))
      (node (ref "U9") (pin "16") (pinfunction "VDD_16") (pintype "power_in"))
      (node (ref "U9") (pin "7") (pinfunction "CEP_7") (pintype "input"))
      (node (ref "U9") (pin "9") (pinfunction "~{PE}_9") (pintype "input"))
    )
    (net (code "96") (name "unconnected-(R5-BOT-Pad2)") (class "Default")
      (node (ref "R5") (pin "2") (pinfunction "BOT_2") (pintype "passive"))
    )
    (net (code "97") (name "unconnected-(R8-Pad8)") (class "Default")
      (node (ref "R8") (pin "8") (pinfunction "8_8") (pintype "passive"))
    )
    (net (code "98") (name "unconnected-(R9-Pad8)") (class "Default")
      (node (ref "R9") (pin "8") (pinfunction "8_8") (pintype "passive"))
    )
    (net (code "99") (name "unconnected-(R10-Pad8)") (class "Default")
      (node (ref "R10") (pin "8") (pinfunction "8_8") (pintype "passive"))
    )
    (net (code "100") (name "unconnected-(R11-Pad8)") (class "Default")
      (node (ref "R11") (pin "8") (pinfunction "8_8") (pintype "passive"))
    )
    (net (code "101") (name "unconnected-(U5A-26-Pad0)") (class "Default")
      (node (ref "U5") (pin "0") (pinfunction "26_0") (pintype "passive"))
    )
    (net (code "102") (name "unconnected-(U9-TC-Pad15)") (class "Default")
      (node (ref "U9") (pin "15") (pinfunction "TC_15") (pintype "output"))
    )
    (net (code "103") (name "unconnected-(Zcnect1-Pad3)") (class "Default")
      (node (ref "Zcnect1") (pin "3") (pinfunction "3_3") (pintype "passive"))
    )
  )
)
